# Schematic.net
KiCad netlist of a schematic drawn in Altium Designer
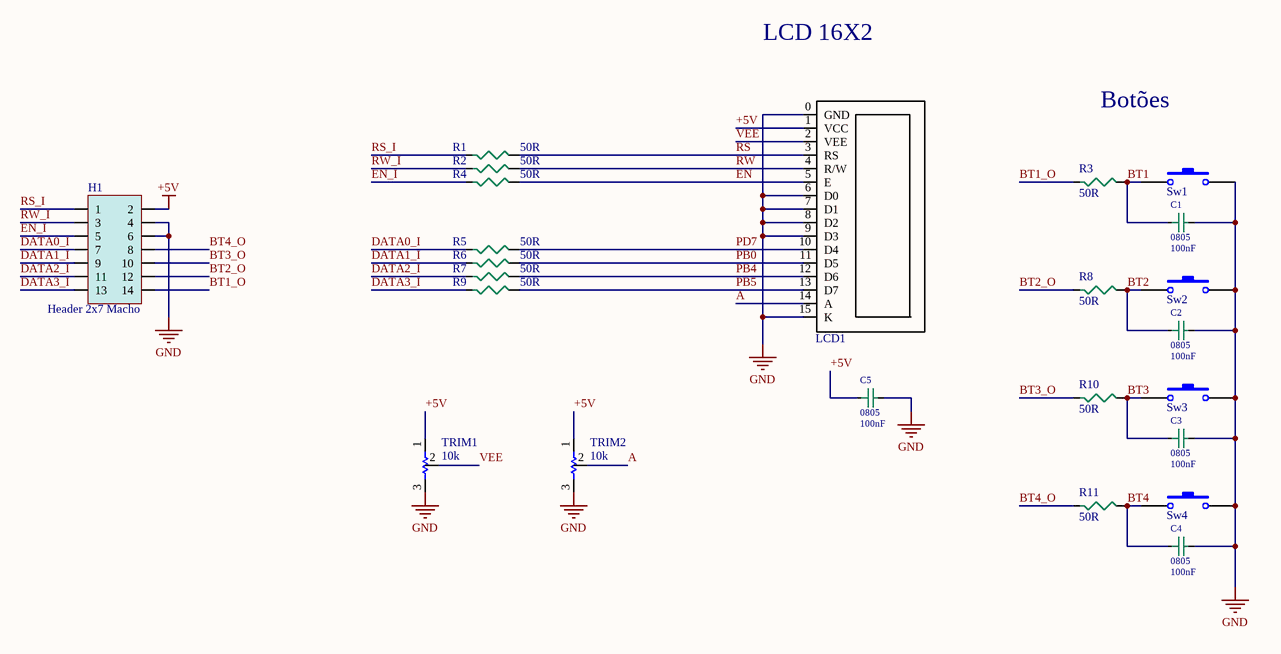
[diagram p0: Schematic.SchDoc]

(export (version "E")
  (design (tool "Eeschema 10.0.6"))
  (components
    (comp (ref "C1")
      (value "0805")
      (footprint "0805C")
      (description "Capacitor SMD 0805")
      (fields (field (name "ALTIUM_VALUE") "100nF"))
      (libsource (lib "RLC_Integrated_Library") (part "Capacitor SMD 0805"))
    )
    (comp (ref "C2")
      (value "0805")
      (footprint "0805C")
      (description "Capacitor SMD 0805")
      (fields (field (name "ALTIUM_VALUE") "100nF"))
      (libsource (lib "RLC_Integrated_Library") (part "Capacitor SMD 0805"))
    )
    (comp (ref "C3")
      (value "0805")
      (footprint "0805C")
      (description "Capacitor SMD 0805")
      (fields (field (name "ALTIUM_VALUE") "100nF"))
      (libsource (lib "RLC_Integrated_Library") (part "Capacitor SMD 0805"))
    )
    (comp (ref "C4")
      (value "0805")
      (footprint "0805C")
      (description "Capacitor SMD 0805")
      (fields (field (name "ALTIUM_VALUE") "100nF"))
      (libsource (lib "RLC_Integrated_Library") (part "Capacitor SMD 0805"))
    )
    (comp (ref "C5")
      (value "0805")
      (footprint "0805C")
      (description "Capacitor SMD 0805")
      (fields (field (name "ALTIUM_VALUE") "100nF"))
      (libsource (lib "RLC_Integrated_Library") (part "Capacitor SMD 0805"))
    )
    (comp (ref "H1")
      (value "Header 2x7 Macho")
      (footprint "HEADER 2X7")
      (libsource (lib "Miscellaneous_Connectors_Integrated_Library") (part "Header 2x7 Macho"))
    )
    (comp (ref "LCD1")
      (value "LCD*")
      (footprint "LCD16X2")
      (description "LCD 16x2")
      (libsource (lib "Jose_lib") (part "LCD 16x2"))
    )
    (comp (ref "R1")
      (value "50R")
      (footprint "0805")
      (description "Resistor SMD 0805 1/8 W")
      (fields (field (name "Comment") "0805"))
      (libsource (lib "RLC_Integrated_Library") (part "Resistor SMD 0805 1/8 W"))
    )
    (comp (ref "R2")
      (value "50R")
      (footprint "0805")
      (description "Resistor SMD 0805 1/8 W")
      (fields (field (name "Comment") "0805"))
      (libsource (lib "RLC_Integrated_Library") (part "Resistor SMD 0805 1/8 W"))
    )
    (comp (ref "R3")
      (value "50R")
      (footprint "0805")
      (description "Resistor SMD 0805 1/8 W")
      (fields (field (name "Comment") "0805"))
      (libsource (lib "RLC_Integrated_Library") (part "Resistor SMD 0805 1/8 W"))
    )
    (comp (ref "R4")
      (value "50R")
      (footprint "0805")
      (description "Resistor SMD 0805 1/8 W")
      (fields (field (name "Comment") "0805"))
      (libsource (lib "RLC_Integrated_Library") (part "Resistor SMD 0805 1/8 W"))
    )
    (comp (ref "R5")
      (value "50R")
      (footprint "0805")
      (description "Resistor SMD 0805 1/8 W")
      (fields (field (name "Comment") "0805"))
      (libsource (lib "RLC_Integrated_Library") (part "Resistor SMD 0805 1/8 W"))
    )
    (comp (ref "R6")
      (value "50R")
      (footprint "0805")
      (description "Resistor SMD 0805 1/8 W")
      (fields (field (name "Comment") "0805"))
      (libsource (lib "RLC_Integrated_Library") (part "Resistor SMD 0805 1/8 W"))
    )
    (comp (ref "R7")
      (value "50R")
      (footprint "0805")
      (description "Resistor SMD 0805 1/8 W")
      (fields (field (name "Comment") "0805"))
      (libsource (lib "RLC_Integrated_Library") (part "Resistor SMD 0805 1/8 W"))
    )
    (comp (ref "R8")
      (value "50R")
      (footprint "0805")
      (description "Resistor SMD 0805 1/8 W")
      (fields (field (name "Comment") "0805"))
      (libsource (lib "RLC_Integrated_Library") (part "Resistor SMD 0805 1/8 W"))
    )
    (comp (ref "R9")
      (value "50R")
      (footprint "0805")
      (description "Resistor SMD 0805 1/8 W")
      (fields (field (name "Comment") "0805"))
      (libsource (lib "RLC_Integrated_Library") (part "Resistor SMD 0805 1/8 W"))
    )
    (comp (ref "R10")
      (value "50R")
      (footprint "0805")
      (description "Resistor SMD 0805 1/8 W")
      (fields (field (name "Comment") "0805"))
      (libsource (lib "RLC_Integrated_Library") (part "Resistor SMD 0805 1/8 W"))
    )
    (comp (ref "R11")
      (value "50R")
      (footprint "0805")
      (description "Resistor SMD 0805 1/8 W")
      (fields (field (name "Comment") "0805"))
      (libsource (lib "RLC_Integrated_Library") (part "Resistor SMD 0805 1/8 W"))
    )
    (comp (ref "Sw1")
      (value "SW_PUSH_BUTTON")
      (footprint "PUSH_BUTTON")
      (description "Switch Push Button")
      (fields (field (name "PUBLISHER") "Altium Limited"))
      (libsource (lib "Jose_lib") (part "SW-PB"))
    )
    (comp (ref "Sw2")
      (value "SW_PUSH_BUTTON")
      (footprint "PUSH_BUTTON")
      (description "Switch Push Button")
      (fields (field (name "PUBLISHER") "Altium Limited"))
      (libsource (lib "Jose_lib") (part "SW-PB"))
    )
    (comp (ref "Sw3")
      (value "SW_PUSH_BUTTON")
      (footprint "PUSH_BUTTON")
      (description "Switch Push Button")
      (fields (field (name "PUBLISHER") "Altium Limited"))
      (libsource (lib "Jose_lib") (part "SW-PB"))
    )
    (comp (ref "Sw4")
      (value "SW_PUSH_BUTTON")
      (footprint "PUSH_BUTTON")
      (description "Switch Push Button")
      (fields (field (name "PUBLISHER") "Altium Limited"))
      (libsource (lib "Jose_lib") (part "SW-PB"))
    )
    (comp (ref "TRIM1")
      (value "10k")
      (footprint "Trimpot Vertical")
      (fields (field (name "Comment") "Trimpot Vertical"))
      (libsource (lib "Jose_lib") (part "Trimpot Vertical"))
    )
    (comp (ref "TRIM2")
      (value "10k")
      (footprint "Trimpot Vertical")
      (fields (field (name "Comment") "Trimpot Vertical"))
      (libsource (lib "Jose_lib") (part "Trimpot Vertical"))
    )
  )
  (nets
    (net (code "1") (name "+5V") (class "Default")
      (node (ref "C5") (pin "1") (pinfunction "1_1") (pintype "passive"))
      (node (ref "H1") (pin "2") (pinfunction "2_2") (pintype "passive"))
      (node (ref "LCD1") (pin "1") (pinfunction "VCC_1") (pintype "passive"))
      (node (ref "TRIM1") (pin "1") (pinfunction "1_1") (pintype "passive"))
      (node (ref "TRIM2") (pin "1") (pinfunction "1_1") (pintype "passive"))
    )
    (net (code "2") (name "/A") (class "Default")
      (node (ref "LCD1") (pin "14") (pinfunction "A_14") (pintype "passive"))
      (node (ref "TRIM2") (pin "2") (pinfunction "2_2") (pintype "passive"))
    )
    (net (code "3") (name "/BT1") (class "Default")
      (node (ref "C1") (pin "1") (pinfunction "1_1") (pintype "passive"))
      (node (ref "R3") (pin "2") (pinfunction "2_2") (pintype "passive"))
      (node (ref "Sw1") (pin "1") (pinfunction "1_1") (pintype "passive"))
    )
    (net (code "4") (name "/BT1_O") (class "Default")
      (node (ref "H1") (pin "14") (pinfunction "14_14") (pintype "passive"))
      (node (ref "R3") (pin "1") (pinfunction "1_1") (pintype "passive"))
    )
    (net (code "5") (name "/BT2") (class "Default")
      (node (ref "C2") (pin "1") (pinfunction "1_1") (pintype "passive"))
      (node (ref "R8") (pin "2") (pinfunction "2_2") (pintype "passive"))
      (node (ref "Sw2") (pin "1") (pinfunction "1_1") (pintype "passive"))
    )
    (net (code "6") (name "/BT2_O") (class "Default")
      (node (ref "H1") (pin "12") (pinfunction "12_12") (pintype "passive"))
      (node (ref "R8") (pin "1") (pinfunction "1_1") (pintype "passive"))
    )
    (net (code "7") (name "/BT3") (class "Default")
      (node (ref "C3") (pin "1") (pinfunction "1_1") (pintype "passive"))
      (node (ref "R10") (pin "2") (pinfunction "2_2") (pintype "passive"))
      (node (ref "Sw3") (pin "1") (pinfunction "1_1") (pintype "passive"))
    )
    (net (code "8") (name "/BT3_O") (class "Default")
      (node (ref "H1") (pin "10") (pinfunction "10_10") (pintype "passive"))
      (node (ref "R10") (pin "1") (pinfunction "1_1") (pintype "passive"))
    )
    (net (code "9") (name "/BT4") (class "Default")
      (node (ref "C4") (pin "1") (pinfunction "1_1") (pintype "passive"))
      (node (ref "R11") (pin "2") (pinfunction "2_2") (pintype "passive"))
      (node (ref "Sw4") (pin "1") (pinfunction "1_1") (pintype "passive"))
    )
    (net (code "10") (name "/BT4_O") (class "Default")
      (node (ref "H1") (pin "8") (pinfunction "8_8") (pintype "passive"))
      (node (ref "R11") (pin "1") (pinfunction "1_1") (pintype "passive"))
    )
    (net (code "11") (name "/DATA0_I") (class "Default")
      (node (ref "H1") (pin "7") (pinfunction "7_7") (pintype "passive"))
      (node (ref "R5") (pin "1") (pinfunction "1_1") (pintype "passive"))
    )
    (net (code "12") (name "/DATA1_I") (class "Default")
      (node (ref "H1") (pin "9") (pinfunction "9_9") (pintype "passive"))
      (node (ref "R6") (pin "1") (pinfunction "1_1") (pintype "passive"))
    )
    (net (code "13") (name "/DATA2_I") (class "Default")
      (node (ref "H1") (pin "11") (pinfunction "11_11") (pintype "passive"))
      (node (ref "R7") (pin "1") (pinfunction "1_1") (pintype "passive"))
    )
    (net (code "14") (name "/DATA3_I") (class "Default")
      (node (ref "H1") (pin "13") (pinfunction "13_13") (pintype "passive"))
      (node (ref "R9") (pin "1") (pinfunction "1_1") (pintype "passive"))
    )
    (net (code "15") (name "/EN") (class "Default")
      (node (ref "LCD1") (pin "5") (pinfunction "E_5") (pintype "passive"))
      (node (ref "R4") (pin "2") (pinfunction "2_2") (pintype "passive"))
    )
    (net (code "16") (name "/EN_I") (class "Default")
      (node (ref "H1") (pin "5") (pinfunction "5_5") (pintype "passive"))
      (node (ref "R4") (pin "1") (pinfunction "1_1") (pintype "passive"))
    )
    (net (code "17") (name "/PB0") (class "Default")
      (node (ref "LCD1") (pin "11") (pinfunction "D5_11") (pintype "passive"))
      (node (ref "R6") (pin "2") (pinfunction "2_2") (pintype "passive"))
    )
    (net (code "18") (name "/PB4") (class "Default")
      (node (ref "LCD1") (pin "12") (pinfunction "D6_12") (pintype "passive"))
      (node (ref "R7") (pin "2") (pinfunction "2_2") (pintype "passive"))
    )
    (net (code "19") (name "/PB5") (class "Default")
      (node (ref "LCD1") (pin "13") (pinfunction "D7_13") (pintype "passive"))
      (node (ref "R9") (pin "2") (pinfunction "2_2") (pintype "passive"))
    )
    (net (code "20") (name "/PD7") (class "Default")
      (node (ref "LCD1") (pin "10") (pinfunction "D4_10") (pintype "passive"))
      (node (ref "R5") (pin "2") (pinfunction "2_2") (pintype "passive"))
    )
    (net (code "21") (name "/RS") (class "Default")
      (node (ref "LCD1") (pin "3") (pinfunction "RS_3") (pintype "passive"))
      (node (ref "R1") (pin "2") (pinfunction "2_2") (pintype "passive"))
    )
    (net (code "22") (name "/RS_I") (class "Default")
      (node (ref "H1") (pin "1") (pinfunction "1_1") (pintype "passive"))
      (node (ref "R1") (pin "1") (pinfunction "1_1") (pintype "passive"))
    )
    (net (code "23") (name "/RW") (class "Default")
      (node (ref "LCD1") (pin "4") (pinfunction "R/W_4") (pintype "passive"))
      (node (ref "R2") (pin "2") (pinfunction "2_2") (pintype "passive"))
    )
    (net (code "24") (name "/RW_I") (class "Default")
      (node (ref "H1") (pin "3") (pinfunction "3_3") (pintype "passive"))
      (node (ref "R2") (pin "1") (pinfunction "1_1") (pintype "passive"))
    )
    (net (code "25") (name "/VEE") (class "Default")
      (node (ref "LCD1") (pin "2") (pinfunction "VEE_2") (pintype "passive"))
      (node (ref "TRIM1") (pin "2") (pinfunction "2_2") (pintype "passive"))
    )
    (net (code "26") (name "GND") (class "Default")
      (node (ref "C1") (pin "2") (pinfunction "2_2") (pintype "passive"))
      (node (ref "C2") (pin "2") (pinfunction "2_2") (pintype "passive"))
      (node (ref "C3") (pin "2") (pinfunction "2_2") (pintype "passive"))
      (node (ref "C4") (pin "2") (pinfunction "2_2") (pintype "passive"))
      (node (ref "C5") (pin "2") (pinfunction "2_2") (pintype "passive"))
      (node (ref "H1") (pin "4") (pinfunction "4_4") (pintype "passive"))
      (node (ref "H1") (pin "6") (pinfunction "6_6") (pintype "passive"))
      (node (ref "LCD1") (pin "0") (pinfunction "GND_0") (pintype "passive"))
      (node (ref "LCD1") (pin "15") (pinfunction "K_15") (pintype "passive"))
      (node (ref "LCD1") (pin "6") (pinfunction "D0_6") (pintype "passive"))
      (node (ref "LCD1") (pin "7") (pinfunction "D1_7") (pintype "passive"))
      (node (ref "LCD1") (pin "8") (pinfunction "D2_8") (pintype "passive"))
      (node (ref "LCD1") (pin "9") (pinfunction "D3_9") (pintype "passive"))
      (node (ref "Sw1") (pin "2") (pinfunction "2_2") (pintype "passive"))
      (node (ref "Sw2") (pin "2") (pinfunction "2_2") (pintype "passive"))
      (node (ref "Sw3") (pin "2") (pinfunction "2_2") (pintype "passive"))
      (node (ref "Sw4") (pin "2") (pinfunction "2_2") (pintype "passive"))
      (node (ref "TRIM1") (pin "3") (pinfunction "3_3") (pintype "passive"))
      (node (ref "TRIM2") (pin "3") (pinfunction "3_3") (pintype "passive"))
    )
  )
)
